# CoproMKII_Connectors.net
KiCad netlist of a schematic drawn in Altium Designer
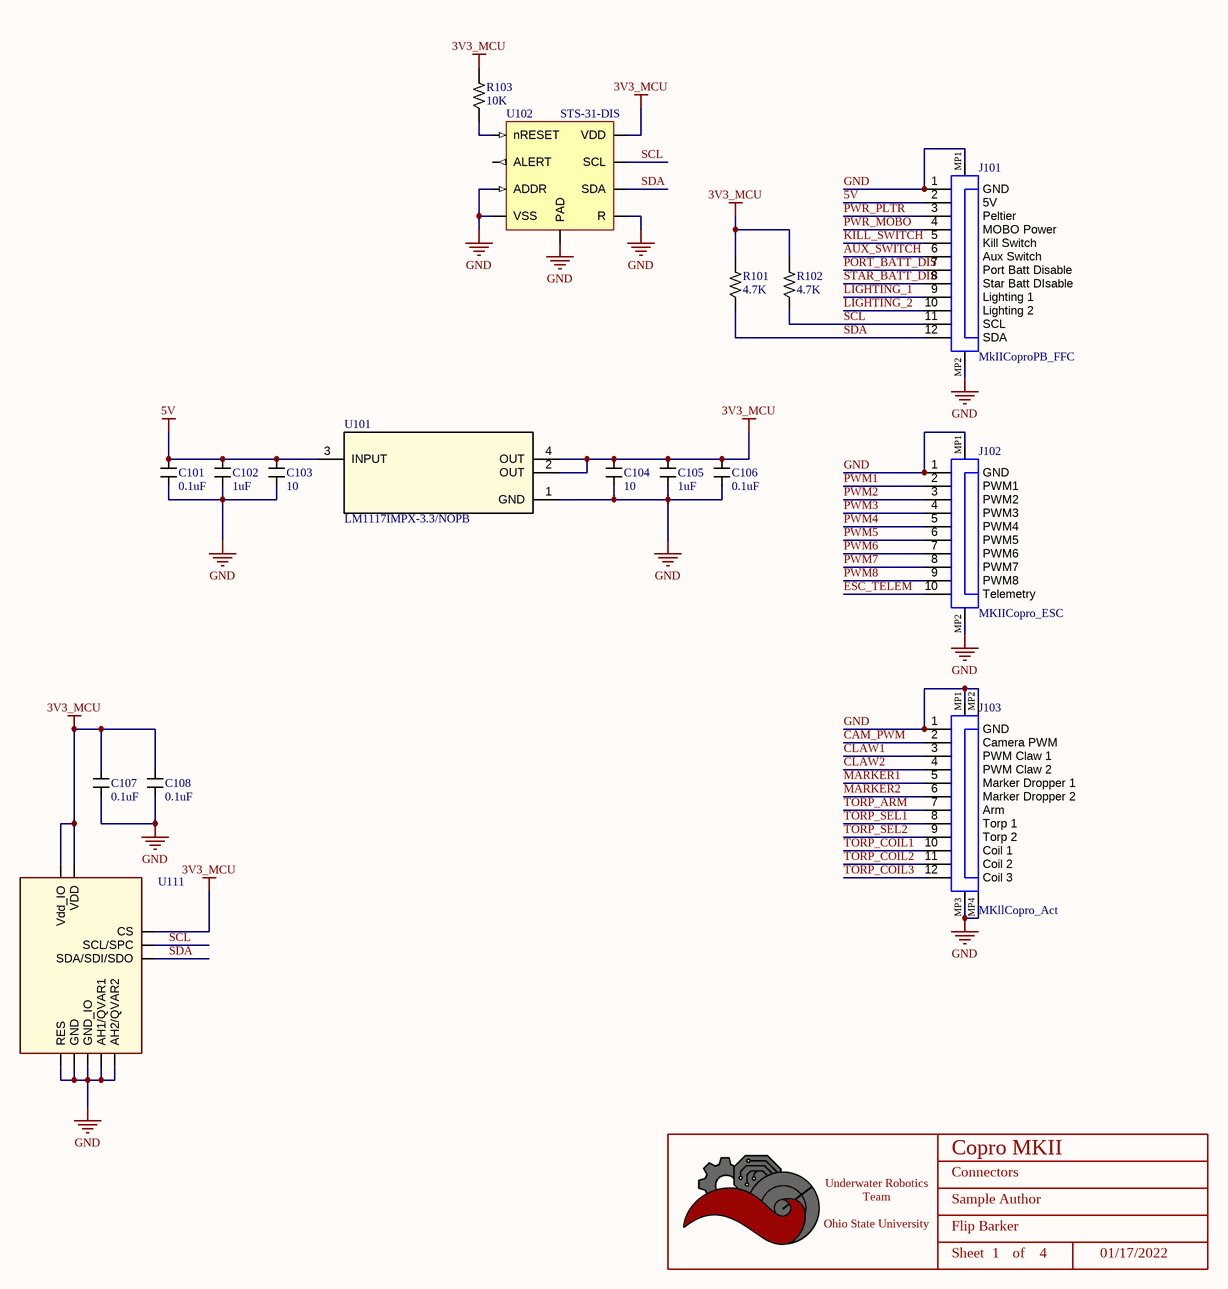
[diagram p0: CoproMKII_Connectors.SchDoc]

(export (version "E")
  (design (tool "Eeschema 10.0.6"))
  (components
    (comp (ref "*")
      (value "Title_Block")
      (footprint "LOGO")
      (description "UWRT Schematic Title Block Template\r\n\r\nCreated June 2021, Dylan Trainor")
      (libsource (lib "UWRT") (part "Title_Block"))
    )
    (comp (ref "C101")
      (value "0.1uF")
      (footprint "CAPACITOR_0603")
      (description "Cap 100nF 6.3V +/-10%\r\nCeramic 0603")
      (fields
        (field (name "TOLERANCE") "+/- 10%")
        (field (name "VOLTAGE") "6.3V")
        (field (name "MADE BY") "Flip B")
      )
      (libsource (lib "Capacitors") (part "CAPACITOR_0.1uF_0603"))
    )
    (comp (ref "C102")
      (value "1uF")
      (footprint "CAPACITOR_0603")
      (description "Cap 1uF 16V +/-10%\r\nCeramic 0603")
      (fields
        (field (name "TOLERANCE") "+/- 10%")
        (field (name "VOLTAGE") "16V")
        (field (name "MADE BY") "Flip B")
      )
      (libsource (lib "Capacitors") (part "CAPACITOR_1uF_0603"))
    )
    (comp (ref "C103")
      (value "10uF Ceramic 6.3V")
      (footprint "CAPACITOR_0603")
      (description "Cap 10uF 6.3V +/-20%\r\nCeramic 0603")
      (fields
        (field (name "TOLERANCE") "+/- 20%")
        (field (name "VOLTAGE") "6.3V")
        (field (name "VALUE (UF)") "10")
        (field (name "MADE BY") "Flip B")
      )
      (libsource (lib "Capacitors") (part "CAPACITOR_10uF_0603"))
    )
    (comp (ref "C104")
      (value "10uF Ceramic 6.3V")
      (footprint "CAPACITOR_0603")
      (description "Cap 10uF 6.3V +/-20%\r\nCeramic 0603")
      (fields
        (field (name "TOLERANCE") "+/- 20%")
        (field (name "VOLTAGE") "6.3V")
        (field (name "VALUE (UF)") "10")
        (field (name "MADE BY") "Flip B")
      )
      (libsource (lib "Capacitors") (part "CAPACITOR_10uF_0603"))
    )
    (comp (ref "C105")
      (value "1uF")
      (footprint "CAPACITOR_0603")
      (description "Cap 1uF 16V +/-10%\r\nCeramic 0603")
      (fields
        (field (name "TOLERANCE") "+/- 10%")
        (field (name "VOLTAGE") "16V")
        (field (name "MADE BY") "Flip B")
      )
      (libsource (lib "Capacitors") (part "CAPACITOR_1uF_0603"))
    )
    (comp (ref "C106")
      (value "0.1uF")
      (footprint "CAPACITOR_0603")
      (description "Cap 100nF 6.3V +/-10%\r\nCeramic 0603")
      (fields
        (field (name "TOLERANCE") "+/- 10%")
        (field (name "VOLTAGE") "6.3V")
        (field (name "MADE BY") "Flip B")
      )
      (libsource (lib "Capacitors") (part "CAPACITOR_0.1uF_0603"))
    )
    (comp (ref "C107")
      (value "0.1uF")
      (footprint "CAPACITOR_0603")
      (description "Cap 100nF 6.3V +/-10%\r\nCeramic 0603")
      (fields
        (field (name "TOLERANCE") "+/- 10%")
        (field (name "VOLTAGE") "6.3V")
        (field (name "MADE BY") "Flip B")
      )
      (libsource (lib "Capacitors") (part "CAPACITOR_0.1uF_0603"))
    )
    (comp (ref "C108")
      (value "0.1uF")
      (footprint "CAPACITOR_0603")
      (description "Cap 100nF 6.3V +/-10%\r\nCeramic 0603")
      (fields
        (field (name "TOLERANCE") "+/- 10%")
        (field (name "VOLTAGE") "6.3V")
        (field (name "MADE BY") "Flip B")
      )
      (libsource (lib "Capacitors") (part "CAPACITOR_0.1uF_0603"))
    )
    (comp (ref "J101")
      (value "MkIICoproPB_FFC")
      (footprint "68611214122")
      (description "WR-FPC SMT ZIF Horizontal Top Contact, pitch 1mm, 12p")
      (fields
        (field (name "MANUFACTURER PART NUMBER") "68611214122")
        (field (name "MANUFACTURER") "Wurth Elektronik")
      )
      (libsource (lib "Connectors") (part "MkIICoproPB_FFC"))
    )
    (comp (ref "J102")
      (value "MKIICopro_ESC")
      (footprint "68611014122")
      (description "WR-FPC SMT ZIF Horizontal Top Contact, pitch 1mm, 10p")
      (fields
        (field (name "MANUFACTURER PART NUMBER") "68611014122")
        (field (name "MANUFACTURER") "Wurth Elektronik")
      )
      (libsource (lib "Connectors") (part "MKIICopro_ESC"))
    )
    (comp (ref "J103")
      (value "MKllCopro_Act")
      (footprint "686112183822")
      (description "WR-FPC SMT ZIF Vertical Type A, pitch 1mm, 12p")
      (fields
        (field (name "MANUFACTURER PART NUMBER") "686112183822")
        (field (name "MANUFACTURER") "Wurth Elektronik")
      )
      (libsource (lib "Connectors") (part "MKllCopro_Act"))
    )
    (comp (ref "R101")
      (value "4.7k Ohm 5% 1/8W")
      (footprint "RESISTOR_0805")
      (description "RES 4.7k OHM 5% 1/8W 0805")
      (fields
        (field (name "TOLERANCE") "+/- 5%")
        (field (name "VALUE  (OHMS)") "4.7K")
        (field (name "MADE BY") "Robert Pafford")
      )
      (libsource (lib "Resistors") (part "RESISTOR_4.7K_0805"))
    )
    (comp (ref "R102")
      (value "4.7k Ohm 5% 1/8W")
      (footprint "RESISTOR_0805")
      (description "RES 4.7k OHM 5% 1/8W 0805")
      (fields
        (field (name "TOLERANCE") "+/- 5%")
        (field (name "VALUE  (OHMS)") "4.7K")
        (field (name "MADE BY") "Robert Pafford")
      )
      (libsource (lib "Resistors") (part "RESISTOR_4.7K_0805"))
    )
    (comp (ref "R103")
      (value "10k Ohm 5% 1/10W")
      (footprint "RESISTOR_0603")
      (description "RES 10k OHM 5% 1/10W 0603")
      (fields
        (field (name "TOLERANCE") "+/- 5%")
        (field (name "VALUE  (OHMS)") "10K")
        (field (name "MADE BY") "Robert Pafford")
      )
      (libsource (lib "Resistors") (part "RESISTOR_10K_0603"))
    )
    (comp (ref "U101")
      (value "LM1117IMPX-3.3/NOPB")
      (footprint "SOT-223-4")
      (description "IC REG LIN 3.3V 800MA SOT223-4")
      (fields
        (field (name "PARTNUMBER") "LM1117IMP-3.3/NOPB")
        (field (name "MANUFACTURER") "Texas Instruments")
        (field (name "CREATED BY") "Dylan T")
      )
      (libsource (lib "Converter") (part "LM1117IMPX-3.3/NOPB"))
    )
    (comp (ref "U102")
      (value "STS-31-DIS")
      (footprint "8-TDFN")
      (description "Temperature Sensor Digital, Local 0°C ~ 90°C 16 b 8-TDFN (2.5x2.5)")
      (fields (field (name "MADE BY") "Robert Pafford"))
      (libsource (lib "Integrated Circuits") (part "STS-31-DIS"))
    )
    (comp (ref "U111")
      (value "ILPS22QSTR")
      (footprint "LGA10R50P2X3_200X200X80")
      (libsource (lib "Integrated Circuits") (part "ILPS22QSTR"))
    )
  )
  (nets
    (net (code "1") (name "/AUX_SWITCH") (class "Default")
      (node (ref "J101") (pin "6") (pinfunction "Aux_Switch_6") (pintype "passive"))
    )
    (net (code "2") (name "/CAM_PWM") (class "Default")
      (node (ref "J103") (pin "2") (pinfunction "Camera_PWM_2") (pintype "passive"))
    )
    (net (code "3") (name "/CLAW1") (class "Default")
      (node (ref "J103") (pin "3") (pinfunction "PWM_Claw_1_3") (pintype "passive"))
    )
    (net (code "4") (name "/CLAW2") (class "Default")
      (node (ref "J103") (pin "4") (pinfunction "PWM_Claw_2_4") (pintype "passive"))
    )
    (net (code "5") (name "/ESC_TELEM") (class "Default")
      (node (ref "J102") (pin "10") (pinfunction "Telemetry_10") (pintype "passive"))
    )
    (net (code "6") (name "/KILL_SWITCH") (class "Default")
      (node (ref "J101") (pin "5") (pinfunction "Kill_Switch_5") (pintype "passive"))
    )
    (net (code "7") (name "/LIGHTING_1") (class "Default")
      (node (ref "J101") (pin "9") (pinfunction "Lighting_1_9") (pintype "passive"))
    )
    (net (code "8") (name "/LIGHTING_2") (class "Default")
      (node (ref "J101") (pin "10") (pinfunction "Lighting_2_10") (pintype "passive"))
    )
    (net (code "9") (name "/MARKER1") (class "Default")
      (node (ref "J103") (pin "5") (pinfunction "Marker_Dropper_1_5") (pintype "passive"))
    )
    (net (code "10") (name "/MARKER2") (class "Default")
      (node (ref "J103") (pin "6") (pinfunction "Marker_Dropper_2_6") (pintype "passive"))
    )
    (net (code "11") (name "/PORT_BATT_DIS") (class "Default")
      (node (ref "J101") (pin "7") (pinfunction "Port_Batt_Disable_7") (pintype "passive"))
    )
    (net (code "12") (name "/PWM1") (class "Default")
      (node (ref "J102") (pin "2") (pinfunction "PWM1_2") (pintype "passive"))
    )
    (net (code "13") (name "/PWM2") (class "Default")
      (node (ref "J102") (pin "3") (pinfunction "PWM2_3") (pintype "passive"))
    )
    (net (code "14") (name "/PWM3") (class "Default")
      (node (ref "J102") (pin "4") (pinfunction "PWM3_4") (pintype "passive"))
    )
    (net (code "15") (name "/PWM4") (class "Default")
      (node (ref "J102") (pin "5") (pinfunction "PWM4_5") (pintype "passive"))
    )
    (net (code "16") (name "/PWM5") (class "Default")
      (node (ref "J102") (pin "6") (pinfunction "PWM5_6") (pintype "passive"))
    )
    (net (code "17") (name "/PWM6") (class "Default")
      (node (ref "J102") (pin "7") (pinfunction "PWM6_7") (pintype "passive"))
    )
    (net (code "18") (name "/PWM7") (class "Default")
      (node (ref "J102") (pin "8") (pinfunction "PWM7_8") (pintype "passive"))
    )
    (net (code "19") (name "/PWM8") (class "Default")
      (node (ref "J102") (pin "9") (pinfunction "PWM8_9") (pintype "passive"))
    )
    (net (code "20") (name "/PWR_MOBO") (class "Default")
      (node (ref "J101") (pin "4") (pinfunction "MOBO_Power_4") (pintype "passive"))
    )
    (net (code "21") (name "/PWR_PLTR") (class "Default")
      (node (ref "J101") (pin "3") (pinfunction "Peltier_3") (pintype "passive"))
    )
    (net (code "22") (name "/SCL") (class "Default")
      (node (ref "J101") (pin "11") (pinfunction "SCL_11") (pintype "passive"))
      (node (ref "R102") (pin "2") (pinfunction "2_2") (pintype "passive"))
      (node (ref "U102") (pin "4") (pinfunction "SCL_4") (pintype "passive"))
      (node (ref "U111") (pin "2") (pinfunction "SCL/SPC_2") (pintype "passive"))
    )
    (net (code "23") (name "/SDA") (class "Default")
      (node (ref "J101") (pin "12") (pinfunction "SDA_12") (pintype "passive"))
      (node (ref "R101") (pin "2") (pinfunction "2_2") (pintype "passive"))
      (node (ref "U102") (pin "1") (pinfunction "SDA_1") (pintype "passive"))
      (node (ref "U111") (pin "4") (pinfunction "SDA/SDI/SDO_4") (pintype "passive"))
    )
    (net (code "24") (name "/STAR_BATT_DIS") (class "Default")
      (node (ref "J101") (pin "8") (pinfunction "Star_Batt_DIsable_8") (pintype "passive"))
    )
    (net (code "25") (name "/TORP_ARM") (class "Default")
      (node (ref "J103") (pin "7") (pinfunction "Arm_7") (pintype "passive"))
    )
    (net (code "26") (name "/TORP_COIL1") (class "Default")
      (node (ref "J103") (pin "10") (pinfunction "Coil_1_10") (pintype "passive"))
    )
    (net (code "27") (name "/TORP_COIL2") (class "Default")
      (node (ref "J103") (pin "11") (pinfunction "Coil_2_11") (pintype "passive"))
    )
    (net (code "28") (name "/TORP_COIL3") (class "Default")
      (node (ref "J103") (pin "12") (pinfunction "Coil_3_12") (pintype "passive"))
    )
    (net (code "29") (name "/TORP_SEL1") (class "Default")
      (node (ref "J103") (pin "8") (pinfunction "Torp_1_8") (pintype "passive"))
    )
    (net (code "30") (name "/TORP_SEL2") (class "Default")
      (node (ref "J103") (pin "9") (pinfunction "Torp_2_9") (pintype "passive"))
    )
    (net (code "31") (name "3V3_MCU") (class "Default")
      (node (ref "C104") (pin "1") (pinfunction "1_1") (pintype "passive"))
      (node (ref "C105") (pin "1") (pinfunction "1_1") (pintype "passive"))
      (node (ref "C106") (pin "1") (pinfunction "1_1") (pintype "passive"))
      (node (ref "C107") (pin "1") (pinfunction "1_1") (pintype "passive"))
      (node (ref "C108") (pin "1") (pinfunction "1_1") (pintype "passive"))
      (node (ref "R101") (pin "1") (pinfunction "1_1") (pintype "passive"))
      (node (ref "R102") (pin "1") (pinfunction "1_1") (pintype "passive"))
      (node (ref "R103") (pin "1") (pinfunction "1_1") (pintype "passive"))
      (node (ref "U101") (pin "2") (pinfunction "OUT_2") (pintype "power_in"))
      (node (ref "U101") (pin "4") (pinfunction "OUT_4") (pintype "power_in"))
      (node (ref "U102") (pin "5") (pinfunction "VDD_5") (pintype "power_in"))
      (node (ref "U111") (pin "1") (pinfunction "Vdd_IO_1") (pintype "passive"))
      (node (ref "U111") (pin "10") (pinfunction "VDD_10") (pintype "passive"))
      (node (ref "U111") (pin "6") (pinfunction "CS_6") (pintype "passive"))
    )
    (net (code "32") (name "5V") (class "Default")
      (node (ref "C101") (pin "1") (pinfunction "1_1") (pintype "passive"))
      (node (ref "C102") (pin "1") (pinfunction "1_1") (pintype "passive"))
      (node (ref "C103") (pin "1") (pinfunction "1_1") (pintype "passive"))
      (node (ref "J101") (pin "2") (pinfunction "5V_2") (pintype "passive"))
      (node (ref "U101") (pin "3") (pinfunction "INPUT_3") (pintype "power_in"))
    )
    (net (code "33") (name "GND") (class "Default")
      (node (ref "C101") (pin "2") (pinfunction "2_2") (pintype "passive"))
      (node (ref "C102") (pin "2") (pinfunction "2_2") (pintype "passive"))
      (node (ref "C103") (pin "2") (pinfunction "2_2") (pintype "passive"))
      (node (ref "C104") (pin "2") (pinfunction "2_2") (pintype "passive"))
      (node (ref "C105") (pin "2") (pinfunction "2_2") (pintype "passive"))
      (node (ref "C106") (pin "2") (pinfunction "2_2") (pintype "passive"))
      (node (ref "C107") (pin "2") (pinfunction "2_2") (pintype "passive"))
      (node (ref "C108") (pin "2") (pinfunction "2_2") (pintype "passive"))
      (node (ref "J101") (pin "1") (pinfunction "GND_1") (pintype "passive"))
      (node (ref "J101") (pin "MP1") (pinfunction "MP1_MP1") (pintype "passive"))
      (node (ref "J101") (pin "MP2") (pinfunction "MP2_MP2") (pintype "passive"))
      (node (ref "J102") (pin "1") (pinfunction "GND_1") (pintype "passive"))
      (node (ref "J102") (pin "MP1") (pinfunction "MP1_MP1") (pintype "passive"))
      (node (ref "J102") (pin "MP2") (pinfunction "MP2_MP2") (pintype "passive"))
      (node (ref "J103") (pin "1") (pinfunction "GND_1") (pintype "passive"))
      (node (ref "J103") (pin "MP1") (pinfunction "MP1_MP1") (pintype "passive"))
      (node (ref "J103") (pin "MP2") (pinfunction "MP2_MP2") (pintype "passive"))
      (node (ref "J103") (pin "MP3") (pinfunction "MP3_MP3") (pintype "passive"))
      (node (ref "J103") (pin "MP4") (pinfunction "MP4_MP4") (pintype "passive"))
      (node (ref "U101") (pin "1") (pinfunction "GND_1") (pintype "power_in"))
      (node (ref "U102") (pin "2") (pinfunction "ADDR_2") (pintype "input"))
      (node (ref "U102") (pin "7") (pinfunction "R_7") (pintype "passive"))
      (node (ref "U102") (pin "8") (pinfunction "VSS_8") (pintype "power_in"))
      (node (ref "U102") (pin "9") (pinfunction "PAD_9") (pintype "power_in"))
      (node (ref "U111") (pin "3") (pinfunction "RES_3") (pintype "passive"))
      (node (ref "U111") (pin "5") (pinfunction "AH2/QVAR2_5") (pintype "passive"))
      (node (ref "U111") (pin "7") (pinfunction "AH1/QVAR1_7") (pintype "passive"))
      (node (ref "U111") (pin "8") (pinfunction "GND_IO_8") (pintype "passive"))
      (node (ref "U111") (pin "9") (pinfunction "GND_9") (pintype "passive"))
    )
    (net (code "34") (name "Net-(U102-nRESET)") (class "Default")
      (node (ref "R103") (pin "2") (pinfunction "2_2") (pintype "passive"))
      (node (ref "U102") (pin "6") (pinfunction "nRESET_6") (pintype "input"))
    )
    (net (code "35") (name "unconnected-(U102-ALERT-Pad3)") (class "Default")
      (node (ref "U102") (pin "3") (pinfunction "ALERT_3") (pintype "output"))
    )
  )
)
